# climate_control.net
KiCad netlist of a schematic drawn in EAGLE
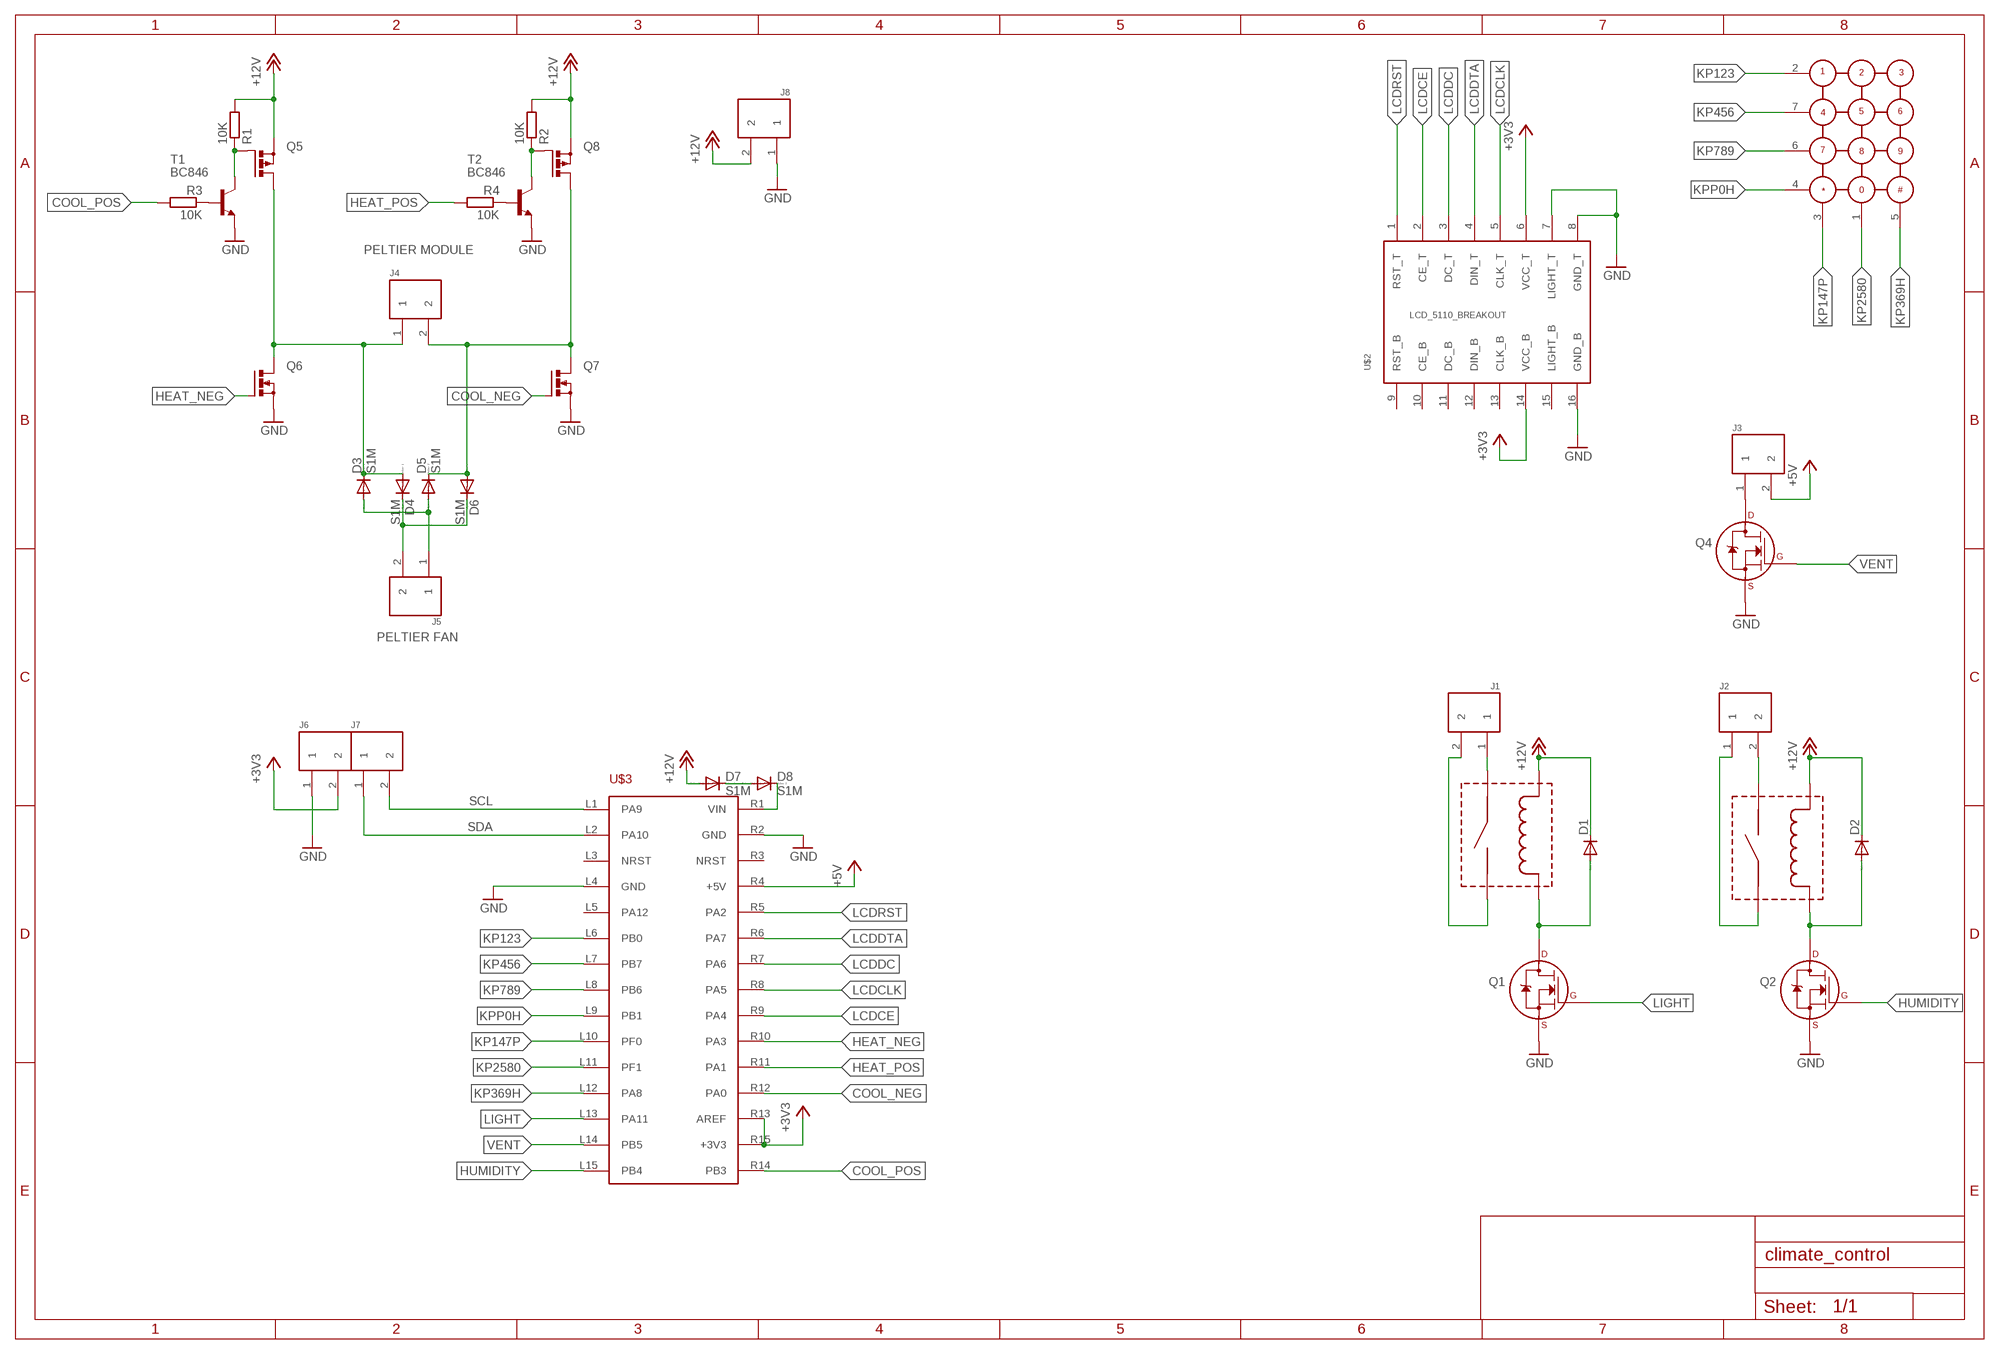
[diagram p0: schematic, sheet 1]

(export (version "E")
  (design (tool "Eeschema 10.0.6"))
  (components
    (comp (ref "D1")
      (value "DIODE-DO-214AC")
      (footprint "eagle-import:DO-214AC")
      (libsource (lib "eagle-import") (part "DIODE-DO-214AC"))
    )
    (comp (ref "D2")
      (value "DIODE-DO-214AC")
      (footprint "eagle-import:DO-214AC")
      (libsource (lib "eagle-import") (part "DIODE-DO-214AC"))
    )
    (comp (ref "D3")
      (value "S1M")
      (footprint "eagle-import:SMA")
      (libsource (lib "eagle-import") (part "S1M"))
    )
    (comp (ref "D4")
      (value "S1M")
      (footprint "eagle-import:SMA")
      (libsource (lib "eagle-import") (part "S1M"))
    )
    (comp (ref "D5")
      (value "S1M")
      (footprint "eagle-import:SMA")
      (libsource (lib "eagle-import") (part "S1M"))
    )
    (comp (ref "D6")
      (value "S1M")
      (footprint "eagle-import:SMA")
      (libsource (lib "eagle-import") (part "S1M"))
    )
    (comp (ref "D7")
      (value "S1M")
      (footprint "eagle-import:SMA")
      (libsource (lib "eagle-import") (part "S1M"))
    )
    (comp (ref "D8")
      (value "S1M")
      (footprint "eagle-import:SMA")
      (libsource (lib "eagle-import") (part "S1M"))
    )
    (comp (ref "J1")
      (value "TERMINAL_PCB_508_X2")
      (footprint "eagle-import:TERMINAL_PCB_508_PITCH")
      (libsource (lib "eagle-import") (part "TERMINAL_PCB_508_X2"))
    )
    (comp (ref "J2")
      (value "TERMINAL_PCB_508_X2")
      (footprint "eagle-import:TERMINAL_PCB_508_PITCH")
      (libsource (lib "eagle-import") (part "TERMINAL_PCB_508_X2"))
    )
    (comp (ref "J3")
      (value "TERMINAL_PCB_508_X2")
      (footprint "eagle-import:TERMINAL_PCB_508_PITCH")
      (libsource (lib "eagle-import") (part "TERMINAL_PCB_508_X2"))
    )
    (comp (ref "J4")
      (value "TERMINAL_PCB_508_X2")
      (footprint "eagle-import:TERMINAL_PCB_508_PITCH")
      (libsource (lib "eagle-import") (part "TERMINAL_PCB_508_X2"))
    )
    (comp (ref "J5")
      (value "TERMINAL_PCB_508_X2")
      (footprint "eagle-import:TERMINAL_PCB_508_PITCH")
      (libsource (lib "eagle-import") (part "TERMINAL_PCB_508_X2"))
    )
    (comp (ref "J6")
      (value "TERMINAL_PCB_508_X2")
      (footprint "eagle-import:TERMINAL_PCB_508_PITCH")
      (libsource (lib "eagle-import") (part "TERMINAL_PCB_508_X2"))
    )
    (comp (ref "J7")
      (value "TERMINAL_PCB_508_X2")
      (footprint "eagle-import:TERMINAL_PCB_508_PITCH")
      (libsource (lib "eagle-import") (part "TERMINAL_PCB_508_X2"))
    )
    (comp (ref "J8")
      (value "TERMINAL_PCB_508_X2")
      (footprint "eagle-import:TERMINAL_PCB_508_PITCH")
      (libsource (lib "eagle-import") (part "TERMINAL_PCB_508_X2"))
    )
    (comp (ref "Q1")
      (value "2N7000_TO92")
      (footprint "eagle-import:TO-92")
      (libsource (lib "eagle-import") (part "2N700_TO920"))
    )
    (comp (ref "Q2")
      (value "2N7000_TO92")
      (footprint "eagle-import:TO-92")
      (libsource (lib "eagle-import") (part "2N700_TO920"))
    )
    (comp (ref "Q4")
      (value "2N7000_TO92")
      (footprint "eagle-import:TO-92")
      (libsource (lib "eagle-import") (part "2N700_TO920"))
    )
    (comp (ref "Q5")
      (value "PMOSFET_PTO220BV")
      (footprint "eagle-import:TO220BV")
      (libsource (lib "eagle-import") (part "PMOSFET_PTO220BV"))
    )
    (comp (ref "Q6")
      (value "PMOSFET_NTO220BV")
      (footprint "eagle-import:TO220BV")
      (libsource (lib "eagle-import") (part "PMOSFET_NTO220BV"))
    )
    (comp (ref "Q7")
      (value "PMOSFET_NTO220BV")
      (footprint "eagle-import:TO220BV")
      (libsource (lib "eagle-import") (part "PMOSFET_NTO220BV"))
    )
    (comp (ref "Q8")
      (value "PMOSFET_PTO220BV")
      (footprint "eagle-import:TO220BV")
      (libsource (lib "eagle-import") (part "PMOSFET_PTO220BV"))
    )
    (comp (ref "R1")
      (value "10K")
      (footprint "eagle-import:R0805")
      (libsource (lib "eagle-import") (part "R-EU_R0805"))
    )
    (comp (ref "R2")
      (value "10K")
      (footprint "eagle-import:R0805")
      (libsource (lib "eagle-import") (part "R-EU_R0805"))
    )
    (comp (ref "R3")
      (value "10K")
      (footprint "eagle-import:R0805")
      (libsource (lib "eagle-import") (part "R-EU_R0805"))
    )
    (comp (ref "R4")
      (value "10K")
      (footprint "eagle-import:R0805")
      (libsource (lib "eagle-import") (part "R-EU_R0805"))
    )
    (comp (ref "T1")
      (value "BC846")
      (footprint "eagle-import:SOT23")
      (libsource (lib "eagle-import") (part "BC846"))
    )
    (comp (ref "T2")
      (value "BC846")
      (footprint "eagle-import:SOT23")
      (libsource (lib "eagle-import") (part "BC846"))
    )
    (comp (ref "U$1")
      (value "KEYPAD12")
      (footprint "eagle-import:KEYPAD12")
      (libsource (lib "eagle-import") (part "KEYPAD12"))
    )
    (comp (ref "U$2")
      (value "LCD_5110_BREAKOUT")
      (footprint "eagle-import:LCD_5110_BREAKOUT")
      (libsource (lib "eagle-import") (part "LCD_5110_BREAKOUT"))
    )
    (comp (ref "U$3")
      (value "NUCLEO_F031")
      (footprint "eagle-import:NUCLEO_30")
      (libsource (lib "eagle-import") (part "NUCLEO_F031"))
    )
    (comp (ref "U$5")
      (value "RELAY_JZC-33F")
      (footprint "eagle-import:RELAY_JZC-33F")
      (libsource (lib "eagle-import") (part "RELAY_JZC-33F"))
    )
    (comp (ref "U$7")
      (value "RELAY_JZC-33F")
      (footprint "eagle-import:RELAY_JZC-33F")
      (libsource (lib "eagle-import") (part "RELAY_JZC-33F"))
    )
  )
  (nets
    (net (code "1") (name "+3V3") (class "Default")
      (node (ref "J6") (pin "2") (pinfunction "2_2") (pintype "bidirectional"))
      (node (ref "U$2") (pin "14") (pinfunction "VCC_B_14") (pintype "power_in"))
      (node (ref "U$2") (pin "6") (pinfunction "VCC_T_6") (pintype "power_in"))
      (node (ref "U$3") (pin "R13") (pinfunction "AREF_R13") (pintype "input"))
      (node (ref "U$3") (pin "R15") (pinfunction "+3V3_R15") (pintype "power_in"))
    )
    (net (code "2") (name "+5V") (class "Default")
      (node (ref "J3") (pin "2") (pinfunction "2_2") (pintype "bidirectional"))
      (node (ref "U$3") (pin "R4") (pinfunction "+5V_R4") (pintype "power_in"))
    )
    (net (code "3") (name "+12V") (class "Default")
      (node (ref "D1") (pin "C") (pinfunction "C_C") (pintype "passive"))
      (node (ref "D2") (pin "C") (pinfunction "C_C") (pintype "passive"))
      (node (ref "D7") (pin "A") (pinfunction "A_A") (pintype "passive"))
      (node (ref "J8") (pin "2") (pinfunction "2_2") (pintype "bidirectional"))
      (node (ref "Q5") (pin "S") (pinfunction "S_S") (pintype "passive"))
      (node (ref "Q8") (pin "S") (pinfunction "S_S") (pintype "passive"))
      (node (ref "R1") (pin "2") (pinfunction "2_2") (pintype "passive"))
      (node (ref "R2") (pin "2") (pinfunction "2_2") (pintype "passive"))
      (node (ref "U$5") (pin "COIL1") (pinfunction "COIL1_COIL1") (pintype "passive"))
      (node (ref "U$7") (pin "COIL2") (pinfunction "COIL2_COIL2") (pintype "passive"))
    )
    (net (code "4") (name "/SCL") (class "Default")
      (node (ref "J7") (pin "2") (pinfunction "2_2") (pintype "bidirectional"))
      (node (ref "U$3") (pin "L1") (pinfunction "PA9_L1") (pintype "bidirectional"))
    )
    (net (code "5") (name "/SDA") (class "Default")
      (node (ref "J7") (pin "1") (pinfunction "1_1") (pintype "bidirectional"))
      (node (ref "U$3") (pin "L2") (pinfunction "PA10_L2") (pintype "bidirectional"))
    )
    (net (code "6") (name "COOL_NEG") (class "Default")
      (node (ref "Q7") (pin "G") (pinfunction "G_G") (pintype "passive"))
      (node (ref "U$3") (pin "R12") (pinfunction "PA0_R12") (pintype "bidirectional"))
    )
    (net (code "7") (name "COOL_POS") (class "Default")
      (node (ref "R3") (pin "2") (pinfunction "2_2") (pintype "passive"))
      (node (ref "U$3") (pin "R14") (pinfunction "PB3_R14") (pintype "bidirectional"))
    )
    (net (code "8") (name "GND") (class "Default")
      (node (ref "J6") (pin "1") (pinfunction "1_1") (pintype "bidirectional"))
      (node (ref "J8") (pin "1") (pinfunction "1_1") (pintype "bidirectional"))
      (node (ref "Q1") (pin "1") (pinfunction "S_1") (pintype "bidirectional"))
      (node (ref "Q2") (pin "1") (pinfunction "S_1") (pintype "bidirectional"))
      (node (ref "Q4") (pin "1") (pinfunction "S_1") (pintype "bidirectional"))
      (node (ref "Q6") (pin "S") (pinfunction "S_S") (pintype "passive"))
      (node (ref "Q7") (pin "S") (pinfunction "S_S") (pintype "passive"))
      (node (ref "T1") (pin "2") (pinfunction "E_2") (pintype "passive"))
      (node (ref "T2") (pin "2") (pinfunction "E_2") (pintype "passive"))
      (node (ref "U$2") (pin "16") (pinfunction "GND_B_16") (pintype "power_in"))
      (node (ref "U$2") (pin "7") (pinfunction "LIGHT_T_7") (pintype "input"))
      (node (ref "U$2") (pin "8") (pinfunction "GND_T_8") (pintype "power_in"))
      (node (ref "U$3") (pin "L4") (pinfunction "GND_L4") (pintype "power_in"))
      (node (ref "U$3") (pin "R2") (pinfunction "GND_R2") (pintype "power_in"))
    )
    (net (code "9") (name "HEAT_NEG") (class "Default")
      (node (ref "Q6") (pin "G") (pinfunction "G_G") (pintype "passive"))
      (node (ref "U$3") (pin "R10") (pinfunction "PA3_R10") (pintype "bidirectional"))
    )
    (net (code "10") (name "HEAT_POS") (class "Default")
      (node (ref "R4") (pin "2") (pinfunction "2_2") (pintype "passive"))
      (node (ref "U$3") (pin "R11") (pinfunction "PA1_R11") (pintype "bidirectional"))
    )
    (net (code "11") (name "HUMIDITY") (class "Default")
      (node (ref "Q2") (pin "2") (pinfunction "G_2") (pintype "tri_state"))
      (node (ref "U$3") (pin "L15") (pinfunction "PB4_L15") (pintype "bidirectional"))
    )
    (net (code "12") (name "KP123") (class "Default")
      (node (ref "U$1") (pin "2") (pinfunction "123_2") (pintype "bidirectional"))
      (node (ref "U$3") (pin "L6") (pinfunction "PB0_L6") (pintype "bidirectional"))
    )
    (net (code "13") (name "KP147P") (class "Default")
      (node (ref "U$1") (pin "3") (pinfunction "147*_3") (pintype "bidirectional"))
      (node (ref "U$3") (pin "L10") (pinfunction "PF0_L10") (pintype "bidirectional"))
    )
    (net (code "14") (name "KP369H") (class "Default")
      (node (ref "U$1") (pin "5") (pinfunction "369#_5") (pintype "bidirectional"))
      (node (ref "U$3") (pin "L12") (pinfunction "PA8_L12") (pintype "bidirectional"))
    )
    (net (code "15") (name "KP456") (class "Default")
      (node (ref "U$1") (pin "7") (pinfunction "456_7") (pintype "bidirectional"))
      (node (ref "U$3") (pin "L7") (pinfunction "PB7_L7") (pintype "bidirectional"))
    )
    (net (code "16") (name "KP789") (class "Default")
      (node (ref "U$1") (pin "6") (pinfunction "789_6") (pintype "bidirectional"))
      (node (ref "U$3") (pin "L8") (pinfunction "PB6_L8") (pintype "bidirectional"))
    )
    (net (code "17") (name "KP2580") (class "Default")
      (node (ref "U$1") (pin "1") (pinfunction "2580_1") (pintype "bidirectional"))
      (node (ref "U$3") (pin "L11") (pinfunction "PF1_L11") (pintype "bidirectional"))
    )
    (net (code "18") (name "KPP0H") (class "Default")
      (node (ref "U$1") (pin "4") (pinfunction "*0#_4") (pintype "bidirectional"))
      (node (ref "U$3") (pin "L9") (pinfunction "PB1_L9") (pintype "bidirectional"))
    )
    (net (code "19") (name "LCDCE") (class "Default")
      (node (ref "U$2") (pin "2") (pinfunction "CE_T_2") (pintype "input"))
      (node (ref "U$3") (pin "R9") (pinfunction "PA4_R9") (pintype "bidirectional"))
    )
    (net (code "20") (name "LCDCLK") (class "Default")
      (node (ref "U$2") (pin "5") (pinfunction "CLK_T_5") (pintype "input"))
      (node (ref "U$3") (pin "R8") (pinfunction "PA5_R8") (pintype "bidirectional"))
    )
    (net (code "21") (name "LCDDC") (class "Default")
      (node (ref "U$2") (pin "3") (pinfunction "DC_T_3") (pintype "input"))
      (node (ref "U$3") (pin "R7") (pinfunction "PA6_R7") (pintype "bidirectional"))
    )
    (net (code "22") (name "LCDDTA") (class "Default")
      (node (ref "U$2") (pin "4") (pinfunction "DIN_T_4") (pintype "input"))
      (node (ref "U$3") (pin "R6") (pinfunction "PA7_R6") (pintype "bidirectional"))
    )
    (net (code "23") (name "LCDRST") (class "Default")
      (node (ref "U$2") (pin "1") (pinfunction "RST_T_1") (pintype "input"))
      (node (ref "U$3") (pin "R5") (pinfunction "PA2_R5") (pintype "bidirectional"))
    )
    (net (code "24") (name "LIGHT") (class "Default")
      (node (ref "Q1") (pin "2") (pinfunction "G_2") (pintype "tri_state"))
      (node (ref "U$3") (pin "L13") (pinfunction "PA11_L13") (pintype "bidirectional"))
    )
    (net (code "25") (name "Net-(D3-PadA)") (class "Default")
      (node (ref "D3") (pin "A") (pinfunction "A_A") (pintype "passive"))
      (node (ref "D5") (pin "A") (pinfunction "A_A") (pintype "passive"))
      (node (ref "J5") (pin "1") (pinfunction "1_1") (pintype "bidirectional"))
    )
    (net (code "26") (name "Net-(D3-PadC)") (class "Default")
      (node (ref "D3") (pin "C") (pinfunction "C_C") (pintype "passive"))
      (node (ref "D4") (pin "A") (pinfunction "A_A") (pintype "passive"))
      (node (ref "J4") (pin "1") (pinfunction "1_1") (pintype "bidirectional"))
      (node (ref "Q5") (pin "D") (pinfunction "D_D") (pintype "passive"))
      (node (ref "Q6") (pin "D") (pinfunction "D_D") (pintype "passive"))
    )
    (net (code "27") (name "Net-(D4-PadC)") (class "Default")
      (node (ref "D4") (pin "C") (pinfunction "C_C") (pintype "passive"))
      (node (ref "D6") (pin "C") (pinfunction "C_C") (pintype "passive"))
      (node (ref "J5") (pin "2") (pinfunction "2_2") (pintype "bidirectional"))
    )
    (net (code "28") (name "Net-(D5-PadC)") (class "Default")
      (node (ref "D5") (pin "C") (pinfunction "C_C") (pintype "passive"))
      (node (ref "D6") (pin "A") (pinfunction "A_A") (pintype "passive"))
      (node (ref "J4") (pin "2") (pinfunction "2_2") (pintype "bidirectional"))
      (node (ref "Q7") (pin "D") (pinfunction "D_D") (pintype "passive"))
      (node (ref "Q8") (pin "D") (pinfunction "D_D") (pintype "passive"))
    )
    (net (code "29") (name "Net-(D7-PadC)") (class "Default")
      (node (ref "D7") (pin "C") (pinfunction "C_C") (pintype "passive"))
      (node (ref "D8") (pin "A") (pinfunction "A_A") (pintype "passive"))
    )
    (net (code "30") (name "Net-(J1-Pad1)") (class "Default")
      (node (ref "J1") (pin "1") (pinfunction "1_1") (pintype "bidirectional"))
      (node (ref "U$5") (pin "CONTACT1") (pinfunction "CONTACT1_CONTACT1") (pintype "passive"))
    )
    (net (code "31") (name "Net-(J1-Pad2)") (class "Default")
      (node (ref "J1") (pin "2") (pinfunction "2_2") (pintype "bidirectional"))
      (node (ref "U$5") (pin "CONTACT2") (pinfunction "CONTACT2_CONTACT2") (pintype "passive"))
    )
    (net (code "32") (name "Net-(J2-Pad1)") (class "Default")
      (node (ref "J2") (pin "1") (pinfunction "1_1") (pintype "bidirectional"))
      (node (ref "U$7") (pin "CONTACT1") (pinfunction "CONTACT1_CONTACT1") (pintype "passive"))
    )
    (net (code "33") (name "Net-(J2-Pad2)") (class "Default")
      (node (ref "J2") (pin "2") (pinfunction "2_2") (pintype "bidirectional"))
      (node (ref "U$7") (pin "CONTACT2") (pinfunction "CONTACT2_CONTACT2") (pintype "passive"))
    )
    (net (code "34") (name "Net-(Q1-D)") (class "Default")
      (node (ref "D1") (pin "A") (pinfunction "A_A") (pintype "passive"))
      (node (ref "Q1") (pin "3") (pinfunction "D_3") (pintype "bidirectional"))
      (node (ref "U$5") (pin "COIL2") (pinfunction "COIL2_COIL2") (pintype "passive"))
    )
    (net (code "35") (name "Net-(Q2-D)") (class "Default")
      (node (ref "D2") (pin "A") (pinfunction "A_A") (pintype "passive"))
      (node (ref "Q2") (pin "3") (pinfunction "D_3") (pintype "bidirectional"))
      (node (ref "U$7") (pin "COIL1") (pinfunction "COIL1_COIL1") (pintype "passive"))
    )
    (net (code "36") (name "Net-(Q4-D)") (class "Default")
      (node (ref "J3") (pin "1") (pinfunction "1_1") (pintype "bidirectional"))
      (node (ref "Q4") (pin "3") (pinfunction "D_3") (pintype "bidirectional"))
    )
    (net (code "37") (name "Net-(T1-B)") (class "Default")
      (node (ref "R3") (pin "1") (pinfunction "1_1") (pintype "passive"))
      (node (ref "T1") (pin "1") (pinfunction "B_1") (pintype "passive"))
    )
    (net (code "38") (name "Net-(T1-C)") (class "Default")
      (node (ref "Q5") (pin "G") (pinfunction "G_G") (pintype "passive"))
      (node (ref "R1") (pin "1") (pinfunction "1_1") (pintype "passive"))
      (node (ref "T1") (pin "3") (pinfunction "C_3") (pintype "passive"))
    )
    (net (code "39") (name "Net-(T2-B)") (class "Default")
      (node (ref "R4") (pin "1") (pinfunction "1_1") (pintype "passive"))
      (node (ref "T2") (pin "1") (pinfunction "B_1") (pintype "passive"))
    )
    (net (code "40") (name "Net-(T2-C)") (class "Default")
      (node (ref "Q8") (pin "G") (pinfunction "G_G") (pintype "passive"))
      (node (ref "R2") (pin "1") (pinfunction "1_1") (pintype "passive"))
      (node (ref "T2") (pin "3") (pinfunction "C_3") (pintype "passive"))
    )
    (net (code "41") (name "Net-(U$3-VIN)") (class "Default")
      (node (ref "D8") (pin "C") (pinfunction "C_C") (pintype "passive"))
      (node (ref "U$3") (pin "R1") (pinfunction "VIN_R1") (pintype "power_in"))
    )
    (net (code "42") (name "VENT") (class "Default")
      (node (ref "Q4") (pin "2") (pinfunction "G_2") (pintype "tri_state"))
      (node (ref "U$3") (pin "L14") (pinfunction "PB5_L14") (pintype "bidirectional"))
    )
    (net (code "43") (name "unconnected-(U$2-CE_B-Pad10)") (class "Default")
      (node (ref "U$2") (pin "10") (pinfunction "CE_B_10") (pintype "input"))
    )
    (net (code "44") (name "unconnected-(U$2-CLK_B-Pad13)") (class "Default")
      (node (ref "U$2") (pin "13") (pinfunction "CLK_B_13") (pintype "input"))
    )
    (net (code "45") (name "unconnected-(U$2-DC_B-Pad11)") (class "Default")
      (node (ref "U$2") (pin "11") (pinfunction "DC_B_11") (pintype "input"))
    )
    (net (code "46") (name "unconnected-(U$2-DIN_B-Pad12)") (class "Default")
      (node (ref "U$2") (pin "12") (pinfunction "DIN_B_12") (pintype "input"))
    )
    (net (code "47") (name "unconnected-(U$2-LIGHT_B-Pad15)") (class "Default")
      (node (ref "U$2") (pin "15") (pinfunction "LIGHT_B_15") (pintype "input"))
    )
    (net (code "48") (name "unconnected-(U$2-RST_B-Pad9)") (class "Default")
      (node (ref "U$2") (pin "9") (pinfunction "RST_B_9") (pintype "input"))
    )
    (net (code "49") (name "unconnected-(U$3-NRST-PadL3)") (class "Default")
      (node (ref "U$3") (pin "L3") (pinfunction "NRST_L3") (pintype "input"))
    )
    (net (code "50") (name "unconnected-(U$3-NRST-PadR3)") (class "Default")
      (node (ref "U$3") (pin "R3") (pinfunction "NRST_R3") (pintype "input"))
    )
    (net (code "51") (name "unconnected-(U$3-PA12-PadL5)") (class "Default")
      (node (ref "U$3") (pin "L5") (pinfunction "PA12_L5") (pintype "bidirectional"))
    )
  )
)
